# SCH_Distance_sensor_with_LED_PWM_2022-05.net
KiCad netlist of a schematic drawn in EasyEDA
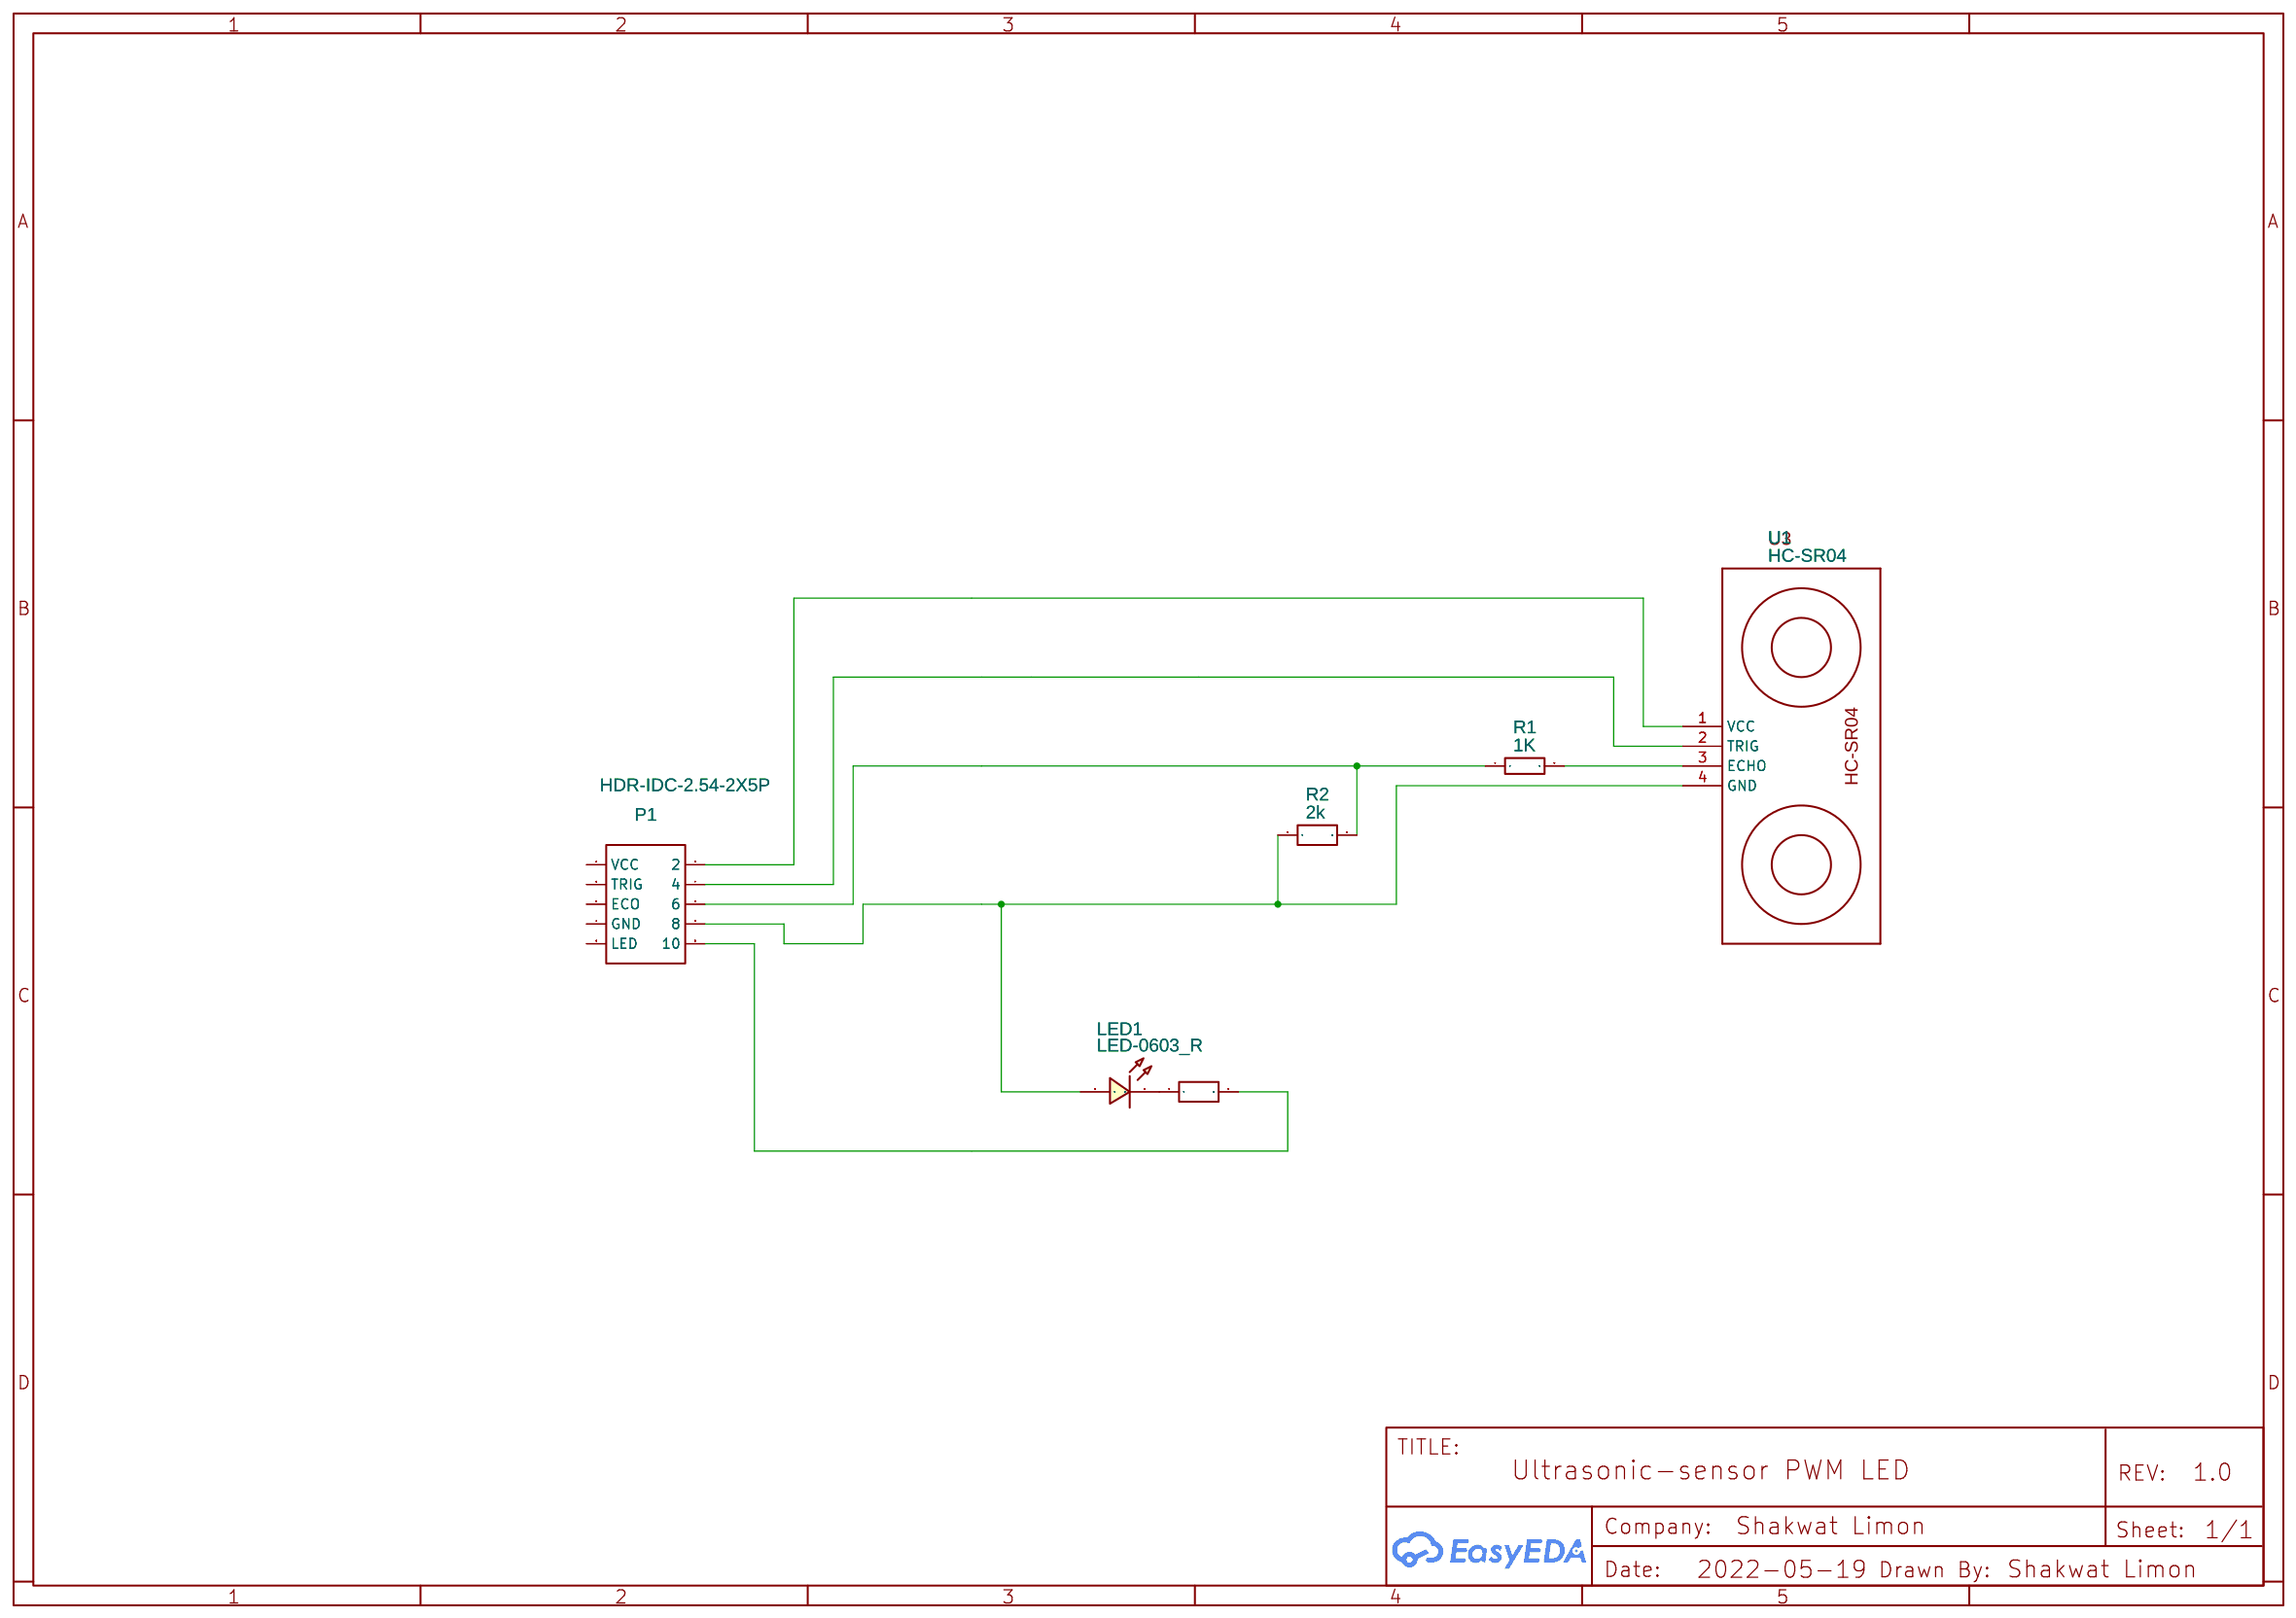
[diagram p0: schematic sheet]

(export (version "E")
  (design (tool "Eeschema 10.0.6"))
  (components
    (comp (ref "LED1")
      (value "LED-0603_R")
      (fields
        (field (name "BOM_Manufacturer Part") "19-217/R6C-AL1M2VY/3T")
        (field (name "BOM_Supplier Part") "C72044")
      )
      (libsource (lib "") (part "LED-0603_R"))
    )
    (comp (ref "P1")
      (value "HDR-IDC-2.54-2X5P")
      (fields
        (field (name "BOM_Manufacturer Part") "IDC Box 2.54mm 2X5P")
        (field (name "BOM_Supplier Part") "C5665")
      )
      (libsource (lib "") (part "HDR-IDC-2.54-2X5P"))
    )
    (comp (ref "R1")
      (value "1K")
      (fields
        (field (name "BOM_Manufacturer Part") "EWWR0003J1K00T9")
        (field (name "BOM_Supplier Part") "C348856")
      )
      (libsource (lib "") (part "resistor 1k ohm"))
    )
    (comp (ref "R2") (value "2k") (libsource (lib "") (part "R_0603_EU")))
    (comp (ref "R3") (value "1k") (libsource (lib "") (part "R_0603_EU")))
    (comp (ref "U1")
      (value "HC-SR04")
      (fields (field (name "BOM_Manufacturer Part") "ServoMotor"))
      (libsource (lib "") (part "HC-SR04"))
    )
  )
  (nets
    (net (code "1") (name "Net-(LED1-Pad2)") (class "Default")
      (node (ref "LED1") (pin "2") (pinfunction "2_2") (pintype "unspecified"))
      (node (ref "R3") (pin "1") (pinfunction "1_1") (pintype "unspecified"))
    )
    (net (code "2") (name "Net-(P1-Pad6)") (class "Default")
      (node (ref "P1") (pin "6") (pinfunction "6_6") (pintype "unspecified"))
      (node (ref "R1") (pin "1") (pinfunction "1_1") (pintype "unspecified"))
      (node (ref "R2") (pin "2") (pinfunction "2_2") (pintype "unspecified"))
    )
    (net (code "3") (name "Net-(P1-Pad10)") (class "Default")
      (node (ref "P1") (pin "10") (pinfunction "10_10") (pintype "unspecified"))
      (node (ref "R3") (pin "2") (pinfunction "2_2") (pintype "unspecified"))
    )
    (net (code "4") (name "Net-(U1-ECHO)") (class "Default")
      (node (ref "R1") (pin "2") (pinfunction "2_2") (pintype "unspecified"))
      (node (ref "U1") (pin "3") (pinfunction "ECHO_3") (pintype "output"))
    )
    (net (code "5") (name "Net-(U1-GND)") (class "Default")
      (node (ref "LED1") (pin "1") (pinfunction "1_1") (pintype "unspecified"))
      (node (ref "P1") (pin "8") (pinfunction "8_8") (pintype "unspecified"))
      (node (ref "R2") (pin "1") (pinfunction "1_1") (pintype "unspecified"))
      (node (ref "U1") (pin "4") (pinfunction "GND_4") (pintype "passive"))
    )
    (net (code "6") (name "Net-(U1-TRIG)") (class "Default")
      (node (ref "P1") (pin "4") (pinfunction "4_4") (pintype "unspecified"))
      (node (ref "U1") (pin "2") (pinfunction "TRIG_2") (pintype "input"))
    )
    (net (code "7") (name "Net-(U1-VCC)") (class "Default")
      (node (ref "P1") (pin "2") (pinfunction "2_2") (pintype "unspecified"))
      (node (ref "U1") (pin "1") (pinfunction "VCC_1") (pintype "passive"))
    )
    (net (code "8") (name "unconnected-(P1-ECO-Pad5)") (class "Default")
      (node (ref "P1") (pin "5") (pinfunction "ECO_5") (pintype "unspecified"))
    )
    (net (code "9") (name "unconnected-(P1-GND-Pad7)") (class "Default")
      (node (ref "P1") (pin "7") (pinfunction "GND_7") (pintype "unspecified"))
    )
    (net (code "10") (name "unconnected-(P1-LED-Pad9)") (class "Default")
      (node (ref "P1") (pin "9") (pinfunction "LED_9") (pintype "unspecified"))
    )
    (net (code "11") (name "unconnected-(P1-TRIG-Pad3)") (class "Default")
      (node (ref "P1") (pin "3") (pinfunction "TRIG_3") (pintype "unspecified"))
    )
    (net (code "12") (name "unconnected-(P1-VCC-Pad1)") (class "Default")
      (node (ref "P1") (pin "1") (pinfunction "VCC_1") (pintype "unspecified"))
    )
  )
)
